# Sheet3.net
KiCad netlist of a schematic drawn in Altium Designer
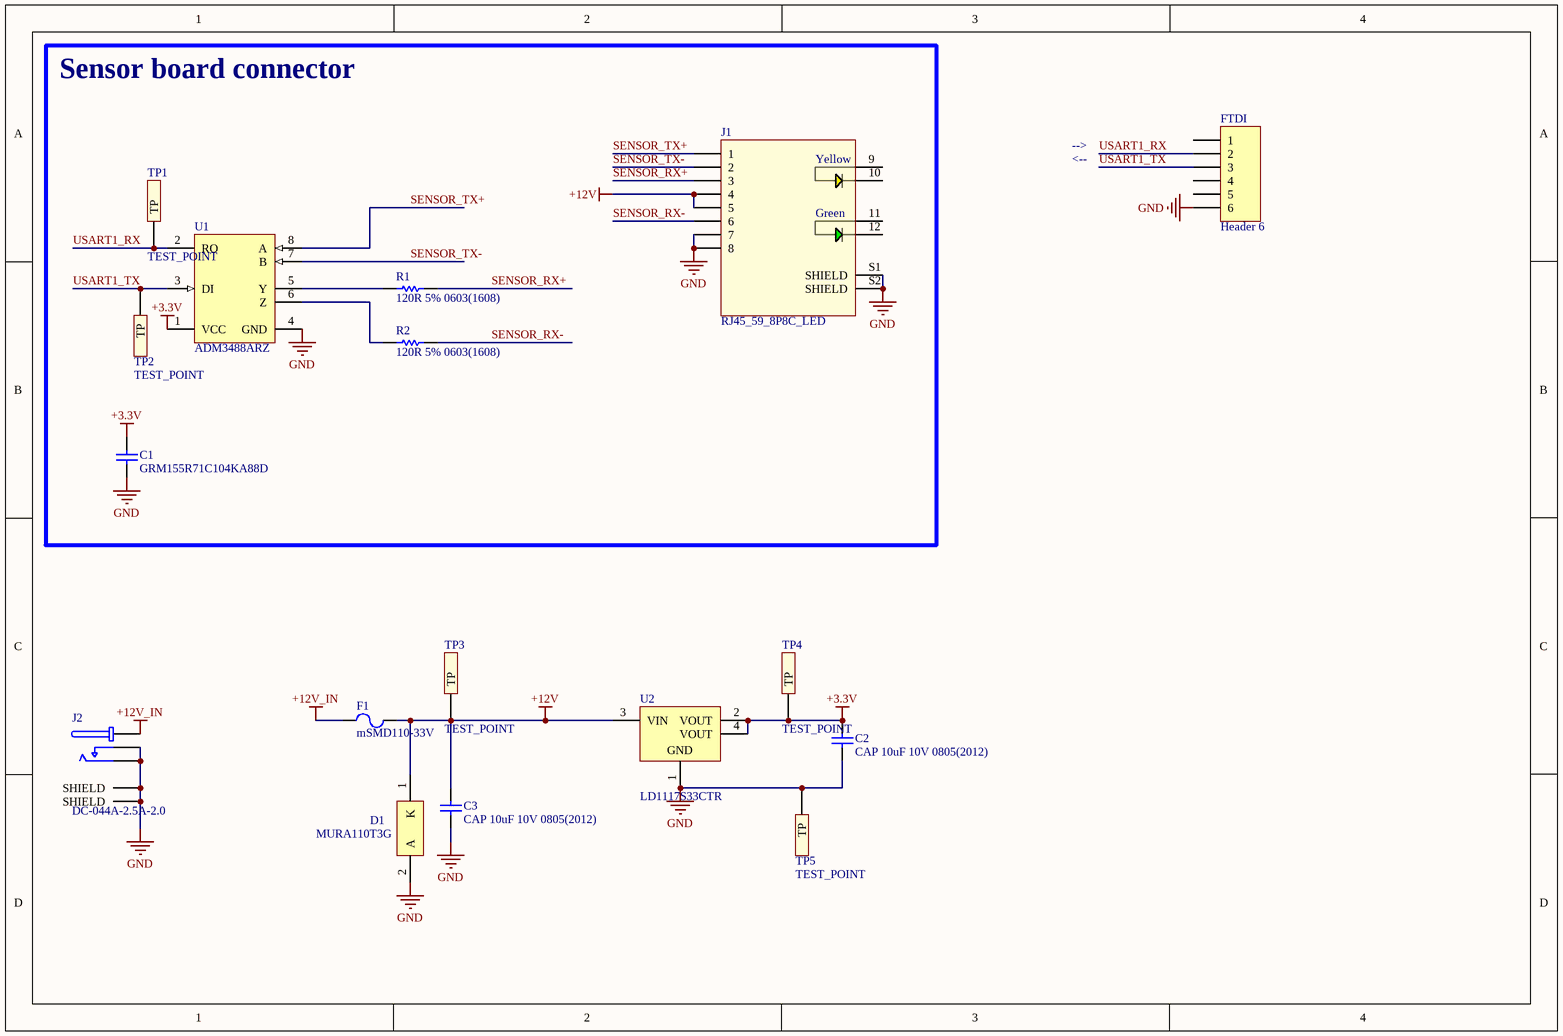
[diagram p0: Sheet3.SchDoc]

(export (version "E")
  (design (tool "Eeschema 10.0.6"))
  (components
    (comp (ref "C1")
      (value "GRM155R71C104KA88D")
      (footprint "CAPC1005X55X25ML05T10")
      (description "Chip Capacitor, 0.1 uF, +/- 10%, 16 V, -55 to 125 degC, 0402 (1005 Metric), RoHS, Tape and Reel")
      (fields (field (name "VOLTAGE") "16V") (field (name "TOLERANCE") "10%"))
      (libsource (lib "Altium Content Vault") (part "CAP-NP-2"))
    )
    (comp (ref "C2")
      (value "CAP 10uF 10V 0805(2012)")
      (footprint "CAPC0805(2012)145_N")
      (description "CAP 10uF 10V ±10% 0805 (2012 Metric) Thickness 1.45mm SMD")
      (fields (field (name "TOLERANCE") "Â±10%"))
      (libsource (lib "Altium Content Vault") (part "CAP"))
    )
    (comp (ref "C3")
      (value "CAP 10uF 10V 0805(2012)")
      (footprint "CAPC0805(2012)145_N")
      (description "CAP 10uF 10V ±10% 0805 (2012 Metric) Thickness 1.45mm SMD")
      (fields (field (name "TOLERANCE") "Â±10%"))
      (libsource (lib "Altium Content Vault") (part "CAP"))
    )
    (comp (ref "D1")
      (value "MURA110T3G")
      (footprint "ONSC-SMA-2-403D-02_V")
      (description "Surface Mount Ultrafast Power Rectifier, 2-Pin SMA, Pb-Free, Tape and Reel")
      (fields (field (name "MANUFACTURER") "On Semiconductor"))
      (libsource (lib "Altium Content Vault") (part "ONSC-D-K1A2-2_A"))
    )
    (comp (ref "F1")
      (value "mSMD110-33V")
      (footprint "SEAANDLAND_1812")
      (description "Surface Mount Fuses 33V 100A 1.1A 2.2A 1812 RoHS")
      (fields (field (name "MANUFACTURER") "Sea & Land Electronic Corp"))
      (libsource (lib "Blinkinlabs") (part "mSMD110-33V"))
    )
    (comp (ref "FTDI")
      (value "Header 6")
      (footprint "HDR1X6")
      (description "Header, 6-Pin")
      (fields (field (name "PUBLISHER") "Altium Limited"))
      (libsource (lib "Miscellaneous Connectors") (part "Header 6"))
    )
    (comp (ref "J1")
      (value "RJ45_59_8P8C_LED")
      (footprint "RJ45_59_8P8C_LED")
      (description "Generic RJ49 jack with LED and without magnetics")
      (fields (field (name "MANUFACTURER") "Unknown/Generic"))
      (libsource (lib "Blinkinlabs") (part "RJ45_59_8P8C_LED"))
    )
    (comp (ref "J2")
      (value "DC-044A-2.5A-2.0")
      (footprint "DC-044A-2.5A-2.0")
      (description "DC Jack, 6mm OD, 2mm ID")
      (fields (field (name "MANUFACTURER") "XKB"))
      (libsource (lib "Blinkinlabs") (part "DC-044A-2.5A-2.0"))
    )
    (comp (ref "R1")
      (value "120R 5% 0603(1608)")
      (footprint "RESC0603(1608)_L")
      (description "120R 0.1W 5% 0603 (1608 Metric)  SMD")
      (fields (field (name "POWER") "0.1 W") (field (name "TOLERANCE") "5 %"))
      (libsource (lib "Altium Content Vault") (part "RES"))
    )
    (comp (ref "R2")
      (value "120R 5% 0603(1608)")
      (footprint "RESC0603(1608)_L")
      (description "120R 0.1W 5% 0603 (1608 Metric)  SMD")
      (fields (field (name "POWER") "0.1 W") (field (name "TOLERANCE") "5 %"))
      (libsource (lib "Altium Content Vault") (part "RES"))
    )
    (comp (ref "TP1")
      (value "TEST_POINT")
      (footprint "TP-SMD-1mm")
      (description "Test point")
      (libsource (lib "Blinkinlabs") (part "TEST_POINT"))
    )
    (comp (ref "TP2")
      (value "TEST_POINT")
      (footprint "TP-SMD-1mm")
      (description "Test point")
      (libsource (lib "") (part "TEST_POINT_1"))
    )
    (comp (ref "TP3")
      (value "TEST_POINT")
      (footprint "TP-SMD-1mm")
      (description "Test point")
      (libsource (lib "Blinkinlabs") (part "TEST_POINT"))
    )
    (comp (ref "TP4")
      (value "TEST_POINT")
      (footprint "TP-SMD-1mm")
      (description "Test point")
      (libsource (lib "Blinkinlabs") (part "TEST_POINT"))
    )
    (comp (ref "TP5")
      (value "TEST_POINT")
      (footprint "TP-SMD-1mm")
      (description "Test point")
      (libsource (lib "") (part "TEST_POINT_1"))
    )
    (comp (ref "U1")
      (value "ADM3488ARZ")
      (footprint "ADI-R-8_L")
      (fields (field (name "MANUFACTURER") "Analog Devices"))
      (libsource (lib "Altium Content Vault") (part "ADI-ADM3488_90-R-8"))
    )
    (comp (ref "U2")
      (value "LD1117S33CTR")
      (footprint "SOT-223_N")
      (description "Fixed Low Drop Positive Voltage Regulator, 3.3V, 4-Pin SOT-223, Tape and Reel")
      (libsource (lib "Altium Content Vault") (part "PM-REG-LD1117-SOT4"))
    )
  )
  (nets
    (net (code "1") (name "+3.3V") (class "Default")
      (node (ref "C1") (pin "2") (pinfunction "2_2") (pintype "passive"))
      (node (ref "C2") (pin "2") (pinfunction "2_2") (pintype "passive"))
      (node (ref "TP4") (pin "1") (pinfunction "TP_1") (pintype "passive"))
      (node (ref "U1") (pin "1") (pinfunction "VCC_1") (pintype "power_in"))
      (node (ref "U2") (pin "2") (pinfunction "VOUT_2") (pintype "power_in"))
      (node (ref "U2") (pin "4") (pinfunction "VOUT_4") (pintype "power_in"))
    )
    (net (code "2") (name "+12V") (class "Default")
      (node (ref "C3") (pin "2") (pinfunction "2_2") (pintype "passive"))
      (node (ref "D1") (pin "1") (pinfunction "K_1") (pintype "passive"))
      (node (ref "F1") (pin "2") (pinfunction "2_2") (pintype "passive"))
      (node (ref "J1") (pin "4") (pinfunction "4_4") (pintype "passive"))
      (node (ref "J1") (pin "5") (pinfunction "5_5") (pintype "passive"))
      (node (ref "TP3") (pin "1") (pinfunction "TP_1") (pintype "passive"))
      (node (ref "U2") (pin "3") (pinfunction "VIN_3") (pintype "power_in"))
    )
    (net (code "3") (name "+12V_IN") (class "Default")
      (node (ref "F1") (pin "1") (pinfunction "1_1") (pintype "passive"))
      (node (ref "J2") (pin "1") (pinfunction "1_1") (pintype "passive"))
    )
    (net (code "4") (name "/SENSOR_RX+") (class "Default")
      (node (ref "J1") (pin "3") (pinfunction "3_3") (pintype "passive"))
      (node (ref "R1") (pin "1") (pinfunction "1_1") (pintype "passive"))
    )
    (net (code "5") (name "/SENSOR_RX-") (class "Default")
      (node (ref "J1") (pin "6") (pinfunction "6_6") (pintype "passive"))
      (node (ref "R2") (pin "1") (pinfunction "1_1") (pintype "passive"))
    )
    (net (code "6") (name "/SENSOR_TX+") (class "Default")
      (node (ref "J1") (pin "1") (pinfunction "1_1") (pintype "passive"))
      (node (ref "U1") (pin "8") (pinfunction "A_8") (pintype "input"))
    )
    (net (code "7") (name "/SENSOR_TX-") (class "Default")
      (node (ref "J1") (pin "2") (pinfunction "2_2") (pintype "passive"))
      (node (ref "U1") (pin "7") (pinfunction "B_7") (pintype "input"))
    )
    (net (code "8") (name "/USART1_RX") (class "Default")
      (node (ref "FTDI") (pin "2") (pinfunction "2_2") (pintype "passive"))
      (node (ref "TP1") (pin "1") (pinfunction "TP_1") (pintype "passive"))
      (node (ref "U1") (pin "2") (pinfunction "RO_2") (pintype "tri_state"))
    )
    (net (code "9") (name "/USART1_TX") (class "Default")
      (node (ref "FTDI") (pin "3") (pinfunction "3_3") (pintype "passive"))
      (node (ref "TP2") (pin "1") (pinfunction "TP_1") (pintype "passive"))
      (node (ref "U1") (pin "3") (pinfunction "DI_3") (pintype "input"))
    )
    (net (code "10") (name "GND") (class "Default")
      (node (ref "C1") (pin "1") (pinfunction "1_1") (pintype "passive"))
      (node (ref "C2") (pin "1") (pinfunction "1_1") (pintype "passive"))
      (node (ref "C3") (pin "1") (pinfunction "1_1") (pintype "passive"))
      (node (ref "D1") (pin "2") (pinfunction "A_2") (pintype "passive"))
      (node (ref "FTDI") (pin "6") (pinfunction "6_6") (pintype "passive"))
      (node (ref "J1") (pin "7") (pinfunction "7_7") (pintype "passive"))
      (node (ref "J1") (pin "8") (pinfunction "8_8") (pintype "passive"))
      (node (ref "J1") (pin "S1") (pinfunction "SHIELD_S1") (pintype "passive"))
      (node (ref "J1") (pin "S2") (pinfunction "SHIELD_S2") (pintype "passive"))
      (node (ref "J2") (pin "2") (pinfunction "2_2") (pintype "passive"))
      (node (ref "J2") (pin "3") (pinfunction "3_3") (pintype "passive"))
      (node (ref "J2") (pin "4") (pinfunction "SHIELD_4") (pintype "passive"))
      (node (ref "J2") (pin "5") (pinfunction "SHIELD_5") (pintype "passive"))
      (node (ref "TP5") (pin "1") (pinfunction "TP_1") (pintype "passive"))
      (node (ref "U1") (pin "4") (pinfunction "GND_4") (pintype "power_in"))
      (node (ref "U2") (pin "1") (pinfunction "GND_1") (pintype "power_in"))
    )
    (net (code "11") (name "Net-(U1-Y)") (class "Default")
      (node (ref "R1") (pin "2") (pinfunction "2_2") (pintype "passive"))
      (node (ref "U1") (pin "5") (pinfunction "Y_5") (pintype "tri_state"))
    )
    (net (code "12") (name "Net-(U1-Z)") (class "Default")
      (node (ref "R2") (pin "2") (pinfunction "2_2") (pintype "passive"))
      (node (ref "U1") (pin "6") (pinfunction "Z_6") (pintype "tri_state"))
    )
    (net (code "13") (name "unconnected-(FTDI-Pad1)") (class "Default")
      (node (ref "FTDI") (pin "1") (pinfunction "1_1") (pintype "passive"))
    )
    (net (code "14") (name "unconnected-(FTDI-Pad4)") (class "Default")
      (node (ref "FTDI") (pin "4") (pinfunction "4_4") (pintype "passive"))
    )
    (net (code "15") (name "unconnected-(FTDI-Pad5)") (class "Default")
      (node (ref "FTDI") (pin "5") (pinfunction "5_5") (pintype "passive"))
    )
    (net (code "16") (name "unconnected-(J1-Green_Anode-Pad11)") (class "Default")
      (node (ref "J1") (pin "11") (pinfunction "Green_Anode_11") (pintype "passive"))
    )
    (net (code "17") (name "unconnected-(J1-Green_Cathode-Pad12)") (class "Default")
      (node (ref "J1") (pin "12") (pinfunction "Green_Cathode_12") (pintype "passive"))
    )
    (net (code "18") (name "unconnected-(J1-Yellow_Anode-Pad9)") (class "Default")
      (node (ref "J1") (pin "9") (pinfunction "Yellow_Anode_9") (pintype "passive"))
    )
    (net (code "19") (name "unconnected-(J1-Yellow_Cathode-Pad10)") (class "Default")
      (node (ref "J1") (pin "10") (pinfunction "Yellow_Cathode_10") (pintype "passive"))
    )
  )
)
